# powerpuck_mini_v4.net
KiCad netlist of a schematic drawn in EAGLE
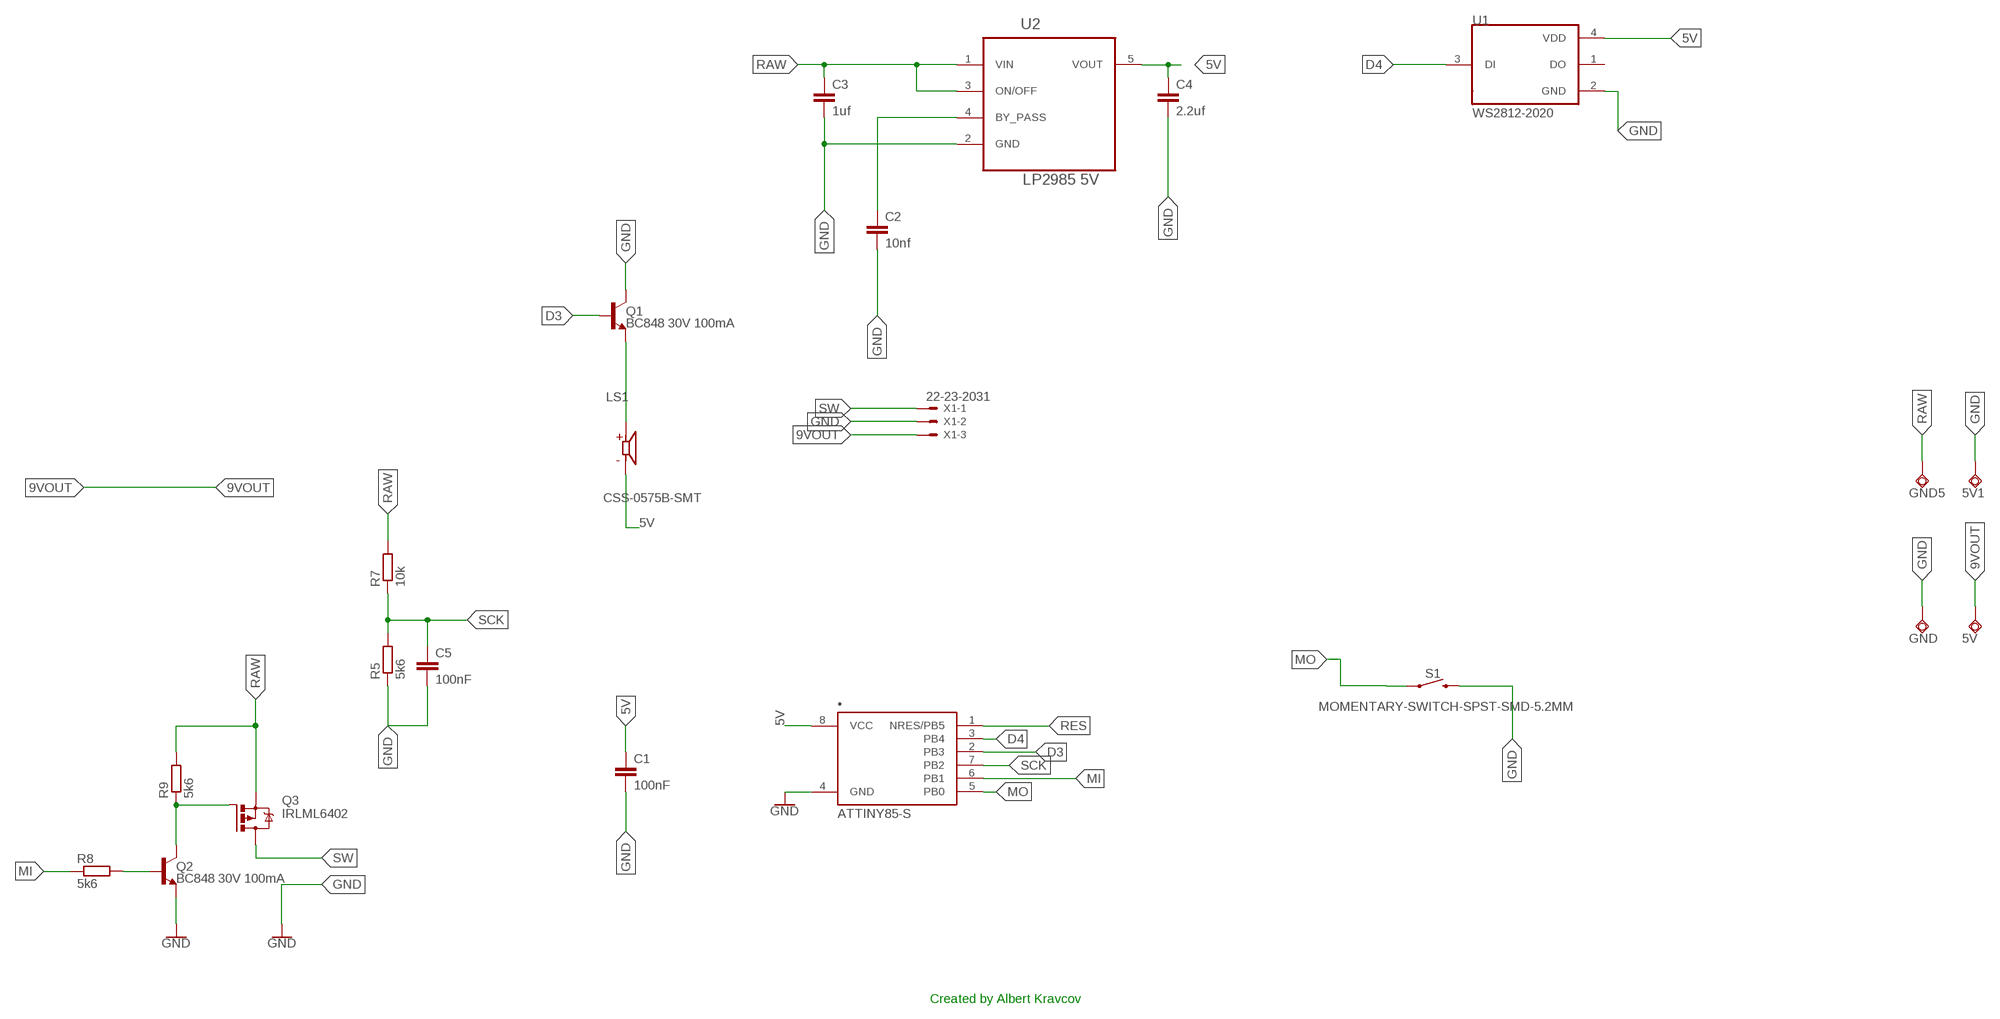
[diagram p0: schematic, sheet 1]

(export (version "E")
  (design (tool "Eeschema 10.0.6"))
  (components
    (comp (ref "5V")
      (value "TPSQTP20R")
      (footprint "eagle-import:TP20R")
      (libsource (lib "eagle-import") (part "TPSQTP20R"))
    )
    (comp (ref "5V1")
      (value "TPSQTP20R")
      (footprint "eagle-import:TP20R")
      (libsource (lib "eagle-import") (part "TPSQTP20R"))
    )
    (comp (ref "C1")
      (value "100nF")
      (footprint "eagle-import:C0603")
      (libsource (lib "eagle-import") (part "resistor_348_C-EUC0603"))
    )
    (comp (ref "C2")
      (value "10nf")
      (footprint "eagle-import:C0805")
      (libsource (lib "eagle-import") (part "C-EUC0805"))
    )
    (comp (ref "C3")
      (value "1uf")
      (footprint "eagle-import:C0805")
      (libsource (lib "eagle-import") (part "C-EUC0805"))
    )
    (comp (ref "C4")
      (value "2.2uf")
      (footprint "eagle-import:C0805")
      (libsource (lib "eagle-import") (part "C-EUC0805"))
    )
    (comp (ref "C5")
      (value "100nF")
      (footprint "eagle-import:C0603")
      (libsource (lib "eagle-import") (part "resistor_348_C-EUC0603"))
    )
    (comp (ref "GND")
      (value "TPSQTP20R")
      (footprint "eagle-import:TP20R")
      (libsource (lib "eagle-import") (part "TPSQTP20R"))
    )
    (comp (ref "GND5")
      (value "TPSQTP20R")
      (footprint "eagle-import:TP20R")
      (libsource (lib "eagle-import") (part "TPSQTP20R"))
    )
    (comp (ref "LS1")
      (value "CSS-0575B-SMT")
      (footprint "eagle-import:CUI_CSS-0575B-SMT")
      (fields (field (name "MF") "CUI Devices") (field (name "MP") "CSS-0575B-SMT-TR"))
      (libsource (lib "eagle-import") (part "CSS-0575B-SMT"))
    )
    (comp (ref "Q1")
      (value "BC848 30V 100mA")
      (footprint "eagle-import:SOT23-3")
      (libsource (lib "eagle-import") (part "TRANS_NPN-MMBT2222AL"))
    )
    (comp (ref "Q2")
      (value "BC848 30V 100mA")
      (footprint "eagle-import:SOT23-3")
      (libsource (lib "eagle-import") (part "TRANS_NPN-MMBT2222AL"))
    )
    (comp (ref "Q3")
      (value "IRLML6402")
      (footprint "eagle-import:MICRO3")
      (libsource (lib "eagle-import") (part "IRLML5203"))
    )
    (comp (ref "R5")
      (value "5k6")
      (footprint "eagle-import:R0603")
      (libsource (lib "eagle-import") (part "R-EU_R0603"))
    )
    (comp (ref "R7")
      (value "10k")
      (footprint "eagle-import:R0603")
      (libsource (lib "eagle-import") (part "R-EU_R0603"))
    )
    (comp (ref "R8")
      (value "5k6")
      (footprint "eagle-import:R0603")
      (libsource (lib "eagle-import") (part "R-EU_R0603"))
    )
    (comp (ref "R9")
      (value "5k6")
      (footprint "eagle-import:R0603")
      (libsource (lib "eagle-import") (part "R-EU_R0603"))
    )
    (comp (ref "S1")
      (value "MOMENTARY-SWITCH-SPST-SMD-5.2MM")
      (footprint "eagle-import:TACTILE_SWITCH_SMD_5.2MM")
      (libsource (lib "eagle-import") (part "MOMENTARY-SWITCH-SPST-SMD-5.2MM"))
    )
    (comp (ref "U1")
      (value "WS2812-2020")
      (footprint "eagle-import:LED_WS2812-2020")
      (fields (field (name "MF") "Worldsemi"))
      (libsource (lib "eagle-import") (part "WS2812-2020"))
    )
    (comp (ref "U2")
      (value "LP2985 5V")
      (footprint "eagle-import:SOT95P284X119-5N")
      (fields (field (name "MF") "National Semiconductor") (field (name "MP") "LP2985AIM550"))
      (libsource (lib "eagle-import") (part "LP2985AIM5-5.0"))
    )
    (comp (ref "X1")
      (value "22-23-2031")
      (footprint "eagle-import:22-23-2031")
      (fields (field (name "MF") "MOLEX"))
      (libsource (lib "eagle-import") (part "22-23-2031"))
    )
    (comp (ref "•")
      (value "ATTINY85-S")
      (footprint "eagle-import:SOIC8_EIAJ_208MIL")
      (libsource (lib "eagle-import") (part "ATTINY85S-"))
    )
  )
  (nets
    (net (code "1") (name "5V") (class "Default")
      (node (ref "C1") (pin "1") (pinfunction "1_1") (pintype "passive"))
      (node (ref "C4") (pin "1") (pinfunction "1_1") (pintype "passive"))
      (node (ref "LS1") (pin "2") (pinfunction "N_2") (pintype "passive"))
      (node (ref "U1") (pin "4") (pinfunction "VDD_4") (pintype "power_in"))
      (node (ref "U2") (pin "5") (pinfunction "VOUT_5") (pintype "output"))
      (node (ref "•") (pin "8") (pinfunction "VCC_8") (pintype "power_in"))
    )
    (net (code "2") (name "9VOUT") (class "Default")
      (node (ref "5V") (pin "TP") (pinfunction "TP_TP") (pintype "input"))
      (node (ref "X1") (pin "3") (pinfunction "S_3") (pintype "passive"))
    )
    (net (code "3") (name "D3") (class "Default")
      (node (ref "Q1") (pin "1") (pinfunction "B_1") (pintype "passive"))
      (node (ref "•") (pin "2") (pinfunction "PB3_2") (pintype "bidirectional"))
    )
    (net (code "4") (name "D4") (class "Default")
      (node (ref "U1") (pin "3") (pinfunction "DI_3") (pintype "input"))
      (node (ref "•") (pin "3") (pinfunction "PB4_3") (pintype "bidirectional"))
    )
    (net (code "5") (name "GND") (class "Default")
      (node (ref "5V1") (pin "TP") (pinfunction "TP_TP") (pintype "input"))
      (node (ref "C1") (pin "2") (pinfunction "2_2") (pintype "passive"))
      (node (ref "C2") (pin "2") (pinfunction "2_2") (pintype "passive"))
      (node (ref "C3") (pin "2") (pinfunction "2_2") (pintype "passive"))
      (node (ref "C4") (pin "2") (pinfunction "2_2") (pintype "passive"))
      (node (ref "C5") (pin "2") (pinfunction "2_2") (pintype "passive"))
      (node (ref "GND") (pin "TP") (pinfunction "TP_TP") (pintype "input"))
      (node (ref "Q1") (pin "3") (pinfunction "C_3") (pintype "passive"))
      (node (ref "Q2") (pin "2") (pinfunction "E_2") (pintype "passive"))
      (node (ref "R5") (pin "1") (pinfunction "1_1") (pintype "passive"))
      (node (ref "S1") (pin "3") (pinfunction "2_3") (pintype "passive"))
      (node (ref "U1") (pin "2") (pinfunction "GND_2") (pintype "power_in"))
      (node (ref "U2") (pin "2") (pinfunction "GND_2") (pintype "passive"))
      (node (ref "X1") (pin "2") (pinfunction "S_2") (pintype "passive"))
      (node (ref "•") (pin "4") (pinfunction "GND_4") (pintype "power_in"))
    )
    (net (code "6") (name "MI") (class "Default")
      (node (ref "R8") (pin "1") (pinfunction "1_1") (pintype "passive"))
      (node (ref "•") (pin "6") (pinfunction "PB1_6") (pintype "bidirectional"))
    )
    (net (code "7") (name "MO") (class "Default")
      (node (ref "S1") (pin "1") (pinfunction "1_1") (pintype "passive"))
      (node (ref "•") (pin "5") (pinfunction "PB0_5") (pintype "bidirectional"))
    )
    (net (code "8") (name "Net-(LS1-P)") (class "Default")
      (node (ref "LS1") (pin "1") (pinfunction "P_1") (pintype "passive"))
      (node (ref "Q1") (pin "2") (pinfunction "E_2") (pintype "passive"))
    )
    (net (code "9") (name "Net-(Q2-B)") (class "Default")
      (node (ref "Q2") (pin "1") (pinfunction "B_1") (pintype "passive"))
      (node (ref "R8") (pin "2") (pinfunction "2_2") (pintype "passive"))
    )
    (net (code "10") (name "Net-(Q2-C)") (class "Default")
      (node (ref "Q2") (pin "3") (pinfunction "C_3") (pintype "passive"))
      (node (ref "Q3") (pin "1") (pinfunction "G_1") (pintype "passive"))
      (node (ref "R9") (pin "1") (pinfunction "1_1") (pintype "passive"))
    )
    (net (code "11") (name "Net-(U2-BY_PASS)") (class "Default")
      (node (ref "C2") (pin "1") (pinfunction "1_1") (pintype "passive"))
      (node (ref "U2") (pin "4") (pinfunction "BY_PASS_4") (pintype "passive"))
    )
    (net (code "12") (name "RAW") (class "Default")
      (node (ref "C3") (pin "1") (pinfunction "1_1") (pintype "passive"))
      (node (ref "GND5") (pin "TP") (pinfunction "TP_TP") (pintype "input"))
      (node (ref "Q3") (pin "2") (pinfunction "S_2") (pintype "passive"))
      (node (ref "R7") (pin "2") (pinfunction "2_2") (pintype "passive"))
      (node (ref "R9") (pin "2") (pinfunction "2_2") (pintype "passive"))
      (node (ref "U2") (pin "1") (pinfunction "VIN_1") (pintype "power_in"))
      (node (ref "U2") (pin "3") (pinfunction "ON/OFF_3") (pintype "input"))
    )
    (net (code "13") (name "RES") (class "Default")
      (node (ref "•") (pin "1") (pinfunction "NRES/PB5_1") (pintype "bidirectional"))
    )
    (net (code "14") (name "SCK") (class "Default")
      (node (ref "C5") (pin "1") (pinfunction "1_1") (pintype "passive"))
      (node (ref "R5") (pin "2") (pinfunction "2_2") (pintype "passive"))
      (node (ref "R7") (pin "1") (pinfunction "1_1") (pintype "passive"))
      (node (ref "•") (pin "7") (pinfunction "PB2_7") (pintype "bidirectional"))
    )
    (net (code "15") (name "SW") (class "Default")
      (node (ref "Q3") (pin "3") (pinfunction "D_3") (pintype "passive"))
      (node (ref "X1") (pin "1") (pinfunction "S_1") (pintype "passive"))
    )
    (net (code "16") (name "unconnected-(U1-DO-Pad1)") (class "Default")
      (node (ref "U1") (pin "1") (pinfunction "DO_1") (pintype "output"))
    )
  )
)
